# hdmi_addon.net
KiCad netlist of a schematic drawn in Altium Designer
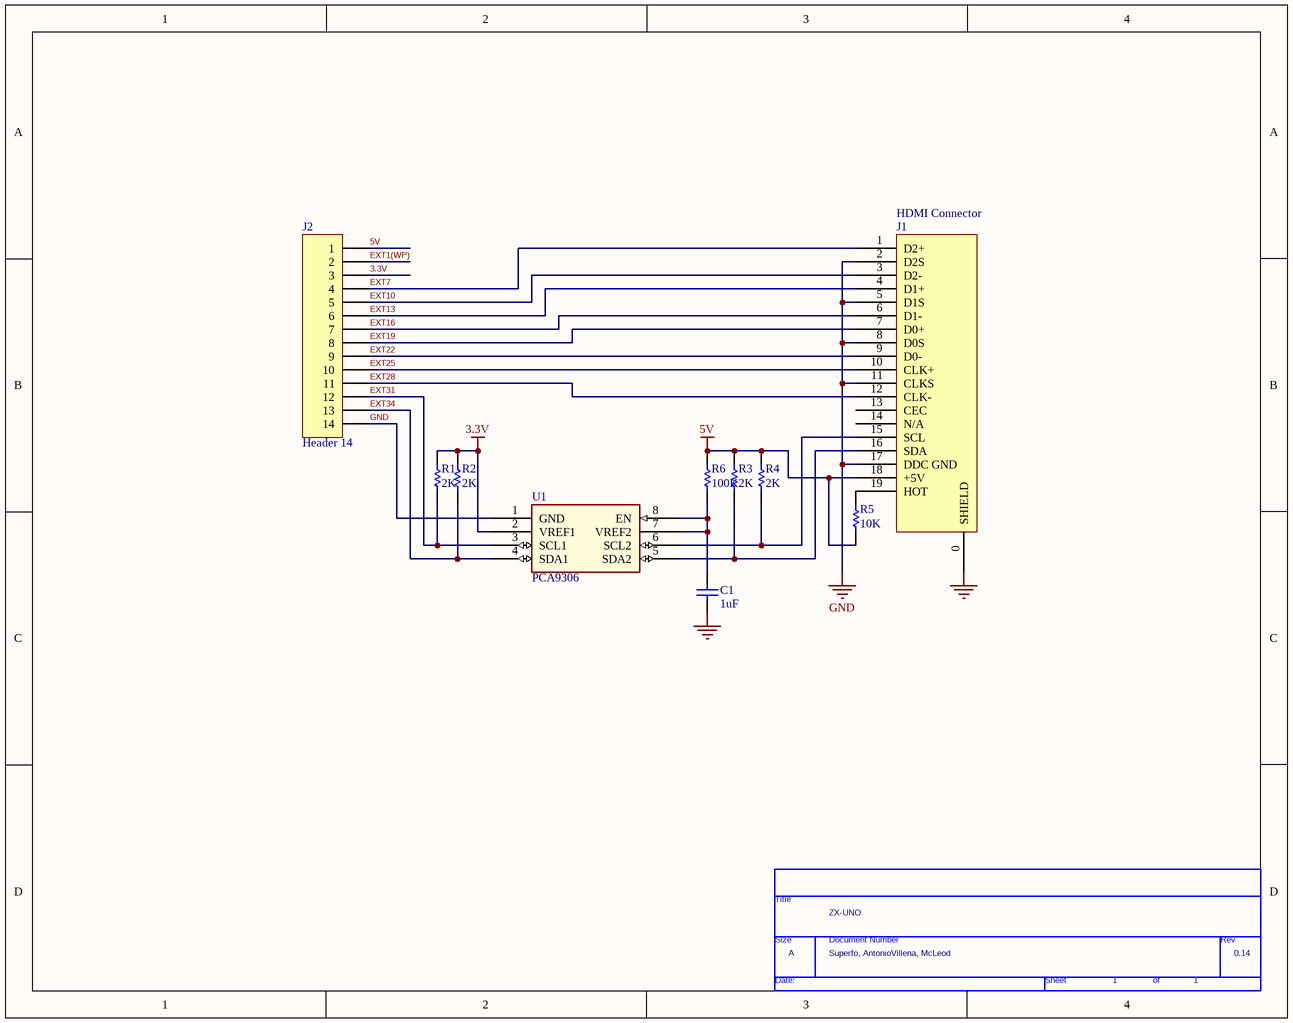
[diagram p0: hdmi addon.SchDoc]

(export (version "E")
  (design (tool "Eeschema 10.0.6"))
  (components
    (comp (ref "*")
      (value "TitleBlock0")
      (fields
        (field (name "PAGE COUNT") "1")
        (field (name "PAGE NUMBER") "1")
        (field (name "PAGE SIZE") "A")
        (field (name "TITLE") "ZX-UNO")
        (field (name "REVCODE") "0.14")
        (field (name "DOC") "Superfo, AntonioVillena, McLeod")
      )
      (libsource (lib "*") (part "TitleBlock0"))
    )
    (comp (ref "C1")
      (value "1uF")
      (footprint "CAPC2012M")
      (description "Capacitor")
      (fields (field (name "Comment") "Cap") (field (name "PUBLISHER") "Altium Limited"))
      (libsource (lib "Miscellaneous Devices") (part "Cap"))
    )
    (comp (ref "J1")
      (value "HDMI Connector")
      (footprint "HDMI 10029449")
      (description "HDMI, SMD, R/A KDMIX-NS1-WS-B")
      (libsource (lib "AltiumDesignLibrary") (part "HDMI-RA-Kycon"))
    )
    (comp (ref "J2")
      (value "Header 14")
      (footprint "HDR1X14")
      (description "Header, 14-Pin")
      (fields (field (name "PUBLISHER") "Altium Limited"))
      (libsource (lib "Miscellaneous Connectors") (part "Header 14"))
    )
    (comp (ref "R1")
      (value "2K")
      (footprint "RESC2012M")
      (description "Resistor")
      (fields (field (name "Comment") "Res1") (field (name "PUBLISHER") "Altium Limited"))
      (libsource (lib "Miscellaneous Devices") (part "Res1"))
    )
    (comp (ref "R2")
      (value "2K")
      (footprint "RESC2012M")
      (description "Resistor")
      (fields (field (name "Comment") "Res1") (field (name "PUBLISHER") "Altium Limited"))
      (libsource (lib "Miscellaneous Devices") (part "Res1"))
    )
    (comp (ref "R3")
      (value "2K")
      (footprint "RESC2012M")
      (description "Resistor")
      (fields (field (name "Comment") "Res1") (field (name "PUBLISHER") "Altium Limited"))
      (libsource (lib "Miscellaneous Devices") (part "Res1"))
    )
    (comp (ref "R4")
      (value "2K")
      (footprint "RESC2012M")
      (description "Resistor")
      (fields (field (name "Comment") "Res1") (field (name "PUBLISHER") "Altium Limited"))
      (libsource (lib "Miscellaneous Devices") (part "Res1"))
    )
    (comp (ref "R5")
      (value "10K")
      (footprint "RESC2012M")
      (description "Resistor")
      (fields (field (name "Comment") "Res1") (field (name "PUBLISHER") "Altium Limited"))
      (libsource (lib "Miscellaneous Devices") (part "Res1"))
    )
    (comp (ref "R6")
      (value "100K")
      (footprint "RESC2012M")
      (description "Resistor")
      (fields (field (name "Comment") "Res1") (field (name "PUBLISHER") "Altium Limited"))
      (libsource (lib "Miscellaneous Devices") (part "Res1"))
    )
    (comp (ref "U1")
      (value "PCA9306")
      (footprint "SOJ.050/8/WB.300/L.200")
      (libsource (lib "Retro Computer") (part "PCA9306"))
    )
  )
  (nets
    (net (code "1") (name "/EXT1(WP)") (class "Default")
      (node (ref "J2") (pin "2") (pinfunction "2_2") (pintype "passive"))
    )
    (net (code "2") (name "/EXT7") (class "Default")
      (node (ref "J1") (pin "1") (pinfunction "D2+_1") (pintype "passive"))
      (node (ref "J2") (pin "4") (pinfunction "4_4") (pintype "passive"))
    )
    (net (code "3") (name "/EXT10") (class "Default")
      (node (ref "J1") (pin "3") (pinfunction "D2-_3") (pintype "passive"))
      (node (ref "J2") (pin "5") (pinfunction "5_5") (pintype "passive"))
    )
    (net (code "4") (name "/EXT13") (class "Default")
      (node (ref "J1") (pin "4") (pinfunction "D1+_4") (pintype "passive"))
      (node (ref "J2") (pin "6") (pinfunction "6_6") (pintype "passive"))
    )
    (net (code "5") (name "/EXT16") (class "Default")
      (node (ref "J1") (pin "6") (pinfunction "D1-_6") (pintype "passive"))
      (node (ref "J2") (pin "7") (pinfunction "7_7") (pintype "passive"))
    )
    (net (code "6") (name "/EXT19") (class "Default")
      (node (ref "J1") (pin "7") (pinfunction "D0+_7") (pintype "passive"))
      (node (ref "J2") (pin "8") (pinfunction "8_8") (pintype "passive"))
    )
    (net (code "7") (name "/EXT22") (class "Default")
      (node (ref "J1") (pin "9") (pinfunction "D0-_9") (pintype "passive"))
      (node (ref "J2") (pin "9") (pinfunction "9_9") (pintype "passive"))
    )
    (net (code "8") (name "/EXT25") (class "Default")
      (node (ref "J1") (pin "10") (pinfunction "CLK+_10") (pintype "passive"))
      (node (ref "J2") (pin "10") (pinfunction "10_10") (pintype "passive"))
    )
    (net (code "9") (name "/EXT28") (class "Default")
      (node (ref "J1") (pin "12") (pinfunction "CLK-_12") (pintype "passive"))
      (node (ref "J2") (pin "11") (pinfunction "11_11") (pintype "passive"))
    )
    (net (code "10") (name "/EXT31") (class "Default")
      (node (ref "J2") (pin "12") (pinfunction "12_12") (pintype "passive"))
      (node (ref "R1") (pin "1") (pinfunction "1_1") (pintype "passive"))
      (node (ref "U1") (pin "3") (pinfunction "SCL1_3") (pintype "bidirectional"))
    )
    (net (code "11") (name "/EXT34") (class "Default")
      (node (ref "J2") (pin "13") (pinfunction "13_13") (pintype "passive"))
      (node (ref "R2") (pin "1") (pinfunction "1_1") (pintype "passive"))
      (node (ref "U1") (pin "4") (pinfunction "SDA1_4") (pintype "bidirectional"))
    )
    (net (code "12") (name "3.3V") (class "Default")
      (node (ref "J2") (pin "3") (pinfunction "3_3") (pintype "passive"))
      (node (ref "R1") (pin "2") (pinfunction "2_2") (pintype "passive"))
      (node (ref "R2") (pin "2") (pinfunction "2_2") (pintype "passive"))
      (node (ref "U1") (pin "2") (pinfunction "VREF1_2") (pintype "power_in"))
    )
    (net (code "13") (name "5V") (class "Default")
      (node (ref "J1") (pin "18") (pinfunction "+5V_18") (pintype "passive"))
      (node (ref "J2") (pin "1") (pinfunction "1_1") (pintype "passive"))
      (node (ref "R3") (pin "2") (pinfunction "2_2") (pintype "passive"))
      (node (ref "R4") (pin "2") (pinfunction "2_2") (pintype "passive"))
      (node (ref "R5") (pin "1") (pinfunction "1_1") (pintype "passive"))
      (node (ref "R6") (pin "2") (pinfunction "2_2") (pintype "passive"))
    )
    (net (code "14") (name "GND") (class "Default")
      (node (ref "C1") (pin "1") (pinfunction "1_1") (pintype "passive"))
      (node (ref "J1") (pin "0") (pinfunction "SHIELD_0") (pintype "passive"))
      (node (ref "J1") (pin "11") (pinfunction "CLKS_11") (pintype "passive"))
      (node (ref "J1") (pin "17") (pinfunction "DDC_GND_17") (pintype "passive"))
      (node (ref "J1") (pin "2") (pinfunction "D2S_2") (pintype "passive"))
      (node (ref "J1") (pin "5") (pinfunction "D1S_5") (pintype "passive"))
      (node (ref "J1") (pin "8") (pinfunction "D0S_8") (pintype "passive"))
      (node (ref "J2") (pin "14") (pinfunction "14_14") (pintype "passive"))
      (node (ref "U1") (pin "1") (pinfunction "GND_1") (pintype "power_in"))
    )
    (net (code "15") (name "Net-(J1-HOT)") (class "Default")
      (node (ref "J1") (pin "19") (pinfunction "HOT_19") (pintype "passive"))
      (node (ref "R5") (pin "2") (pinfunction "2_2") (pintype "passive"))
    )
    (net (code "16") (name "Net-(J1-SCL)") (class "Default")
      (node (ref "J1") (pin "15") (pinfunction "SCL_15") (pintype "passive"))
      (node (ref "R4") (pin "1") (pinfunction "1_1") (pintype "passive"))
      (node (ref "U1") (pin "6") (pinfunction "SCL2_6") (pintype "bidirectional"))
    )
    (net (code "17") (name "Net-(J1-SDA)") (class "Default")
      (node (ref "J1") (pin "16") (pinfunction "SDA_16") (pintype "passive"))
      (node (ref "R3") (pin "1") (pinfunction "1_1") (pintype "passive"))
      (node (ref "U1") (pin "5") (pinfunction "SDA2_5") (pintype "bidirectional"))
    )
    (net (code "18") (name "Net-(U1-EN)") (class "Default")
      (node (ref "C1") (pin "2") (pinfunction "2_2") (pintype "passive"))
      (node (ref "R6") (pin "1") (pinfunction "1_1") (pintype "passive"))
      (node (ref "U1") (pin "7") (pinfunction "VREF2_7") (pintype "power_in"))
      (node (ref "U1") (pin "8") (pinfunction "EN_8") (pintype "input"))
    )
    (net (code "19") (name "unconnected-(J1-CEC-Pad13)") (class "Default")
      (node (ref "J1") (pin "13") (pinfunction "CEC_13") (pintype "passive"))
    )
    (net (code "20") (name "unconnected-(J1-N{slash}A-Pad14)") (class "Default")
      (node (ref "J1") (pin "14") (pinfunction "N/A_14") (pintype "passive"))
    )
  )
)
